# all_pcb.net
KiCad netlist of a schematic drawn in EasyEDA Pro
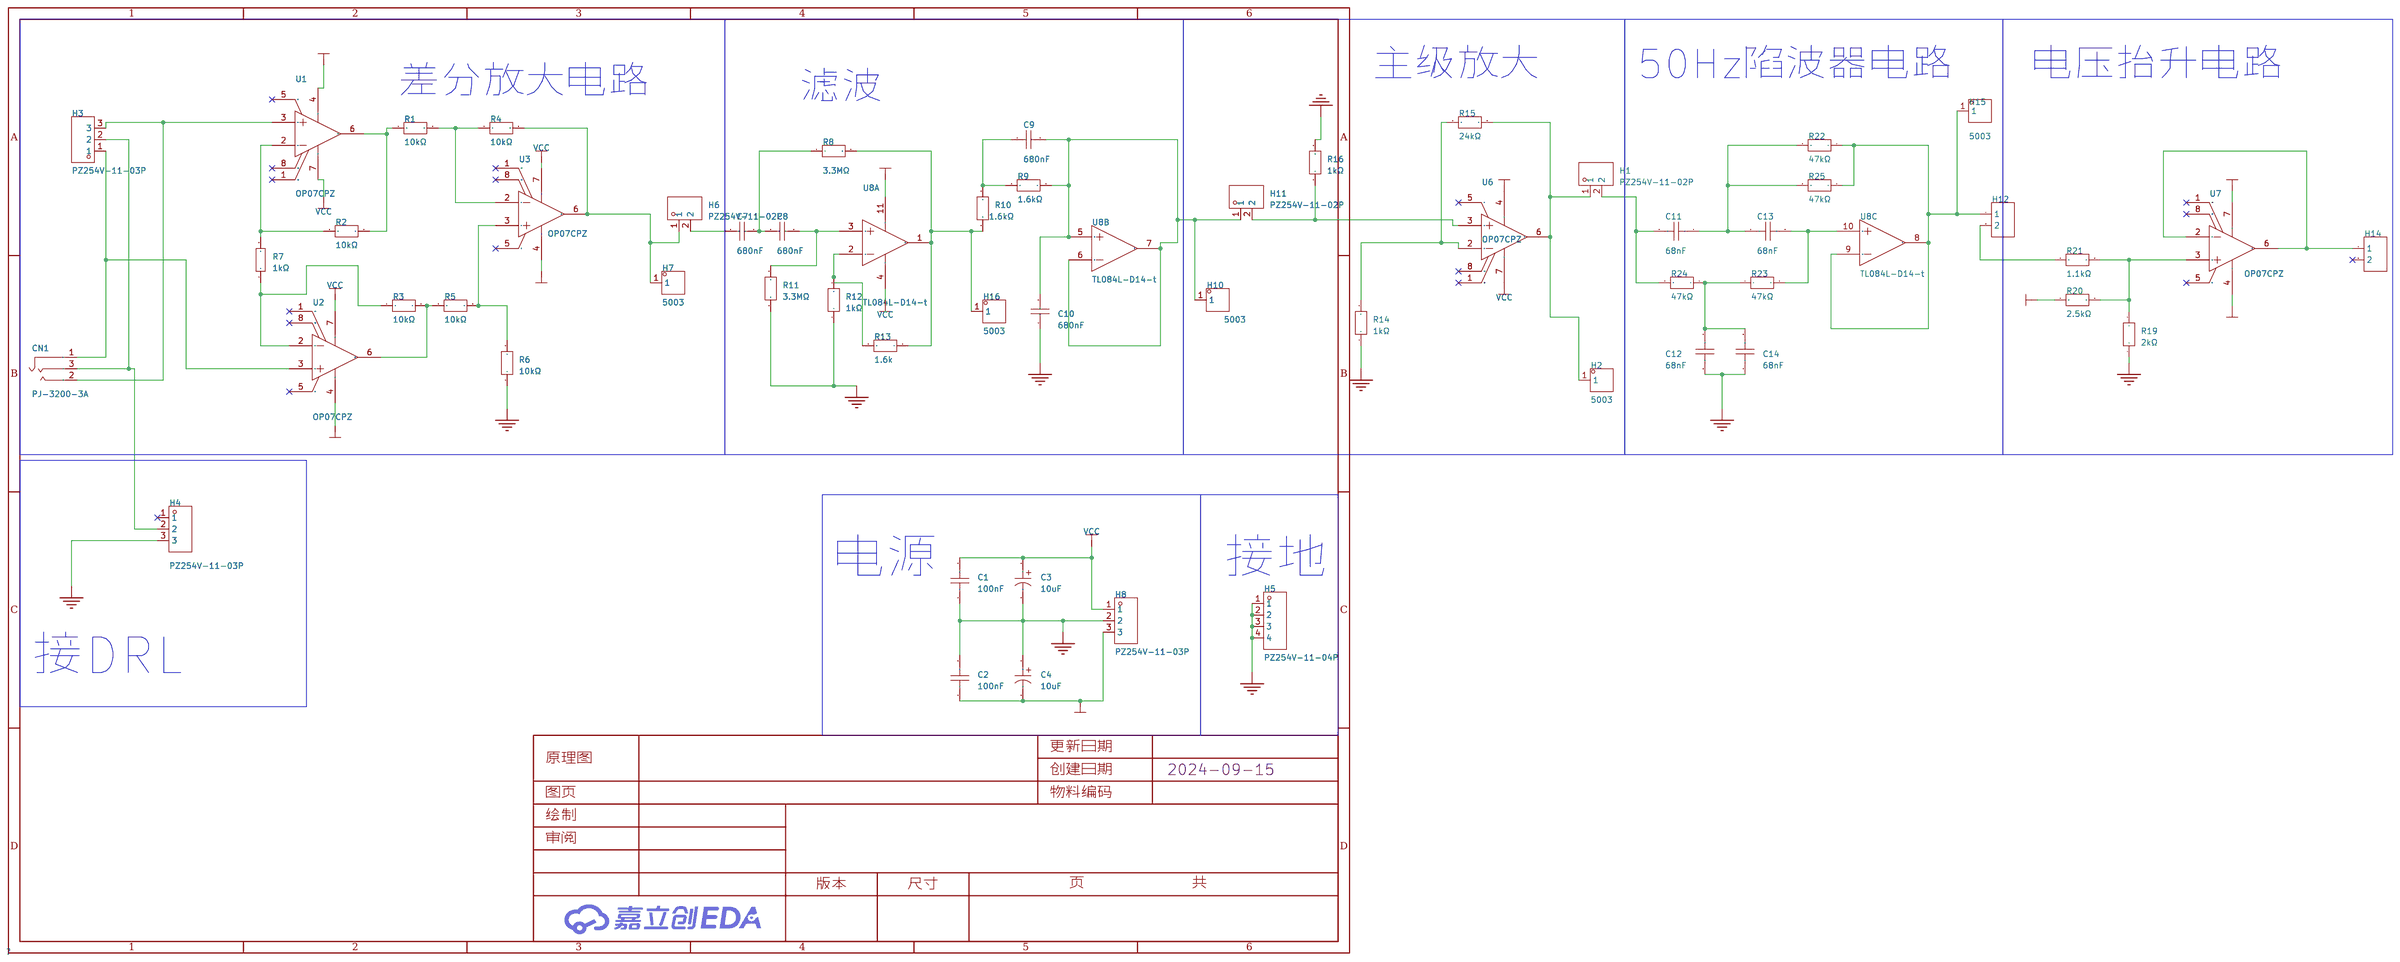
[diagram p0: schematic sheet]

(export (version "E")
  (design (tool "Eeschema 10.0.6"))
  (components
    (comp (ref "C1")
      (value "100nF")
      (footprint "easyedapro:CAP-TH_L13.0-W6.0-P10.0-D0.6")
      (description "容值:100nF;精度:±10%;电压(AC):275V;等级:X2;")
      (fields (field (name "Manufacturer Part") "1X2H410K275-11") (field (name "Manufacturer") "BM(丰明电容)"))
      (libsource (lib "easyedapro") (part "1X2H410K275-11"))
    )
    (comp (ref "C2")
      (value "100nF")
      (footprint "easyedapro:CAP-TH_L13.0-W6.0-P10.0-D0.6")
      (description "容值:100nF;精度:±10%;电压(AC):275V;等级:X2;")
      (fields (field (name "Manufacturer Part") "1X2H410K275-11") (field (name "Manufacturer") "BM(丰明电容)"))
      (libsource (lib "easyedapro") (part "1X2H410K275-11"))
    )
    (comp (ref "C3")
      (value "10uF")
      (footprint "easyedapro:CAP-TH_BD10.0-P5.00-D0.6-FD")
      (description "容值:10uF;精度:±20%;额定电压:250V;纹波电流:175mA@120Hz;等效串联电阻:-;")
      (fields
        (field (name "Manufacturer Part") "UCS2E100MPD1TD")
        (field (name "Manufacturer") "Nichicon(尼吉康)")
      )
      (libsource (lib "easyedapro") (part "UCS2E100MPD1TD"))
    )
    (comp (ref "C4")
      (value "10uF")
      (footprint "easyedapro:CAP-TH_BD10.0-P5.00-D0.6-FD")
      (description "容值:10uF;精度:±20%;额定电压:250V;纹波电流:175mA@120Hz;等效串联电阻:-;")
      (fields
        (field (name "Manufacturer Part") "UCS2E100MPD1TD")
        (field (name "Manufacturer") "Nichicon(尼吉康)")
      )
      (libsource (lib "easyedapro") (part "UCS2E100MPD1TD"))
    )
    (comp (ref "C7")
      (value "680nF")
      (footprint "easyedapro:CAP-TH_L7.5-W6.5-P5.00-D0.5")
      (description "容值:680nF;精度:±5%;额定电压:100V;工作温度:-40°C~+110°C;")
      (fields (field (name "Manufacturer Part") "PE684J2A0502") (field (name "Manufacturer") "KYET(科雅)"))
      (libsource (lib "easyedapro") (part "PE684J2A0502"))
    )
    (comp (ref "C8")
      (value "680nF")
      (footprint "easyedapro:CAP-TH_L7.5-W6.5-P5.00-D0.5")
      (description "容值:680nF;精度:±5%;额定电压:100V;工作温度:-40°C~+110°C;")
      (fields (field (name "Manufacturer Part") "PE684J2A0502") (field (name "Manufacturer") "KYET(科雅)"))
      (libsource (lib "easyedapro") (part "PE684J2A0502"))
    )
    (comp (ref "C9")
      (value "680nF")
      (footprint "easyedapro:CAP-TH_L7.5-W6.5-P5.00-D0.5")
      (description "容值:680nF;精度:±5%;额定电压:100V;工作温度:-40°C~+110°C;")
      (fields (field (name "Manufacturer Part") "PE684J2A0502") (field (name "Manufacturer") "KYET(科雅)"))
      (libsource (lib "easyedapro") (part "PE684J2A0502"))
    )
    (comp (ref "C10")
      (value "680nF")
      (footprint "easyedapro:CAP-TH_L7.5-W6.5-P5.00-D0.5")
      (description "容值:680nF;精度:±5%;额定电压:100V;工作温度:-40°C~+110°C;")
      (fields (field (name "Manufacturer Part") "PE684J2A0502") (field (name "Manufacturer") "KYET(科雅)"))
      (libsource (lib "easyedapro") (part "PE684J2A0502"))
    )
    (comp (ref "C11")
      (value "68nF")
      (footprint "easyedapro:CAP-TH_L5.1-W3.8-P5.08-D1.2")
      (description "容值:100nF;精度:±10%;额定电压:630V;温度系数:X7R;")
      (fields (field (name "Manufacturer Part") "C322C104KBR5TA") (field (name "Manufacturer") "KEMET(基美)"))
      (libsource (lib "easyedapro") (part "C322C104KBR5TA"))
    )
    (comp (ref "C12")
      (value "68nF")
      (footprint "easyedapro:CAP-TH_L18.0-W8.0-P15.00-D0.8")
      (description "容值:200nF;精度:±20%;电压(AC):305V;等级:X2;")
      (fields (field (name "Manufacturer Part") "B32922H3204M") (field (name "Manufacturer") "TDK"))
      (libsource (lib "easyedapro") (part "B32922H3204M"))
    )
    (comp (ref "C13")
      (value "68nF")
      (footprint "easyedapro:CAP-TH_L5.1-W3.8-P5.08-D1.2")
      (description "容值:100nF;精度:±10%;额定电压:630V;温度系数:X7R;")
      (fields (field (name "Manufacturer Part") "C322C104KBR5TA") (field (name "Manufacturer") "KEMET(基美)"))
      (libsource (lib "easyedapro") (part "C322C104KBR5TA"))
    )
    (comp (ref "C14")
      (value "68nF")
      (footprint "easyedapro:CAP-TH_L5.1-W3.8-P5.08-D1.2")
      (description "容值:100nF;精度:±10%;额定电压:630V;温度系数:X7R;")
      (fields (field (name "Manufacturer Part") "C322C104KBR5TA") (field (name "Manufacturer") "KEMET(基美)"))
      (libsource (lib "easyedapro") (part "C322C104KBR5TA"))
    )
    (comp (ref "CN1")
      (value "PJ-3200-3A")
      (footprint "easyedapro:AUDIO-TH_PJ-3200-3A")
      (description "连接器类型:3.5mm耳机座;额定电流:500mA;额定电压:30V;工作温度范围:-20°C~+70°C;")
      (fields (field (name "Manufacturer") "韩国韩荣"))
      (libsource (lib "easyedapro") (part "PJ-3200-3A"))
    )
    (comp (ref "H1")
      (value "PZ254V-11-02P")
      (footprint "easyedapro:HDR-TH_2P-P2.54-V-M")
      (fields (field (name "Manufacturer") "XFCN(兴飞)"))
      (libsource (lib "easyedapro") (part "PZ254V-11-02P"))
    )
    (comp (ref "H2")
      (value "5003")
      (footprint "easyedapro:TEST-TH_BD2.54-P1.39")
      (description "类型:测试环;全长/全高:7.62mm;工作高度:-;接触电阻:-;弹性寿命:-;额定电流:-;额定电压:-;触头材质:磷青铜;触头镀层:-;工作温度范围:-;")
      (fields (field (name "Manufacturer") "Keystone"))
      (libsource (lib "easyedapro") (part "5003"))
    )
    (comp (ref "H3")
      (value "PZ254V-11-03P")
      (footprint "easyedapro:HDR-TH_3P-P2.54-V-M")
      (fields (field (name "Manufacturer") "XFCN(兴飞)"))
      (libsource (lib "easyedapro") (part "PZ254V-11-03P_C2937625"))
    )
    (comp (ref "H4")
      (value "PZ254V-11-03P")
      (footprint "easyedapro:HDR-TH_3P-P2.54-V-M")
      (fields (field (name "Manufacturer") "XFCN(兴飞)"))
      (libsource (lib "easyedapro") (part "PZ254V-11-03P_C2937625"))
    )
    (comp (ref "H5")
      (value "PZ254V-11-04P")
      (footprint "easyedapro:HDR-TH_4P-P2.54-V-M")
      (fields (field (name "Manufacturer") "XFCN(兴飞)"))
      (libsource (lib "easyedapro") (part "PZ254V-11-04P_C2691448"))
    )
    (comp (ref "H6")
      (value "PZ254V-11-02P")
      (footprint "easyedapro:HDR-TH_2P-P2.54-V-M")
      (fields (field (name "Manufacturer") "XFCN(兴飞)"))
      (libsource (lib "easyedapro") (part "PZ254V-11-02P"))
    )
    (comp (ref "H7")
      (value "5003")
      (footprint "easyedapro:TEST-TH_BD2.54-P1.39")
      (description "类型:测试环;全长/全高:7.62mm;工作高度:-;接触电阻:-;弹性寿命:-;额定电流:-;额定电压:-;触头材质:磷青铜;触头镀层:-;工作温度范围:-;")
      (fields (field (name "Manufacturer") "Keystone"))
      (libsource (lib "easyedapro") (part "5003"))
    )
    (comp (ref "H8")
      (value "PZ254V-11-03P")
      (footprint "easyedapro:HDR-TH_3P-P2.54-V-M")
      (fields (field (name "Manufacturer") "XFCN(兴飞)"))
      (libsource (lib "easyedapro") (part "PZ254V-11-03P_C2937625"))
    )
    (comp (ref "H10")
      (value "5003")
      (footprint "easyedapro:TEST-TH_BD2.54-P1.39")
      (description "类型:测试环;全长/全高:7.62mm;工作高度:-;接触电阻:-;弹性寿命:-;额定电流:-;额定电压:-;触头材质:磷青铜;触头镀层:-;工作温度范围:-;")
      (fields (field (name "Manufacturer") "Keystone"))
      (libsource (lib "easyedapro") (part "5003"))
    )
    (comp (ref "H11")
      (value "PZ254V-11-02P")
      (footprint "easyedapro:HDR-TH_2P-P2.54-V-M")
      (fields (field (name "Manufacturer") "XFCN(兴飞)"))
      (libsource (lib "easyedapro") (part "PZ254V-11-02P"))
    )
    (comp (ref "H12")
      (value "~")
      (footprint "easyedapro:HDR-TH_2P-P2.54-V-F")
      (libsource (lib "easyedapro") (part "Header-Female-2.54_1x2"))
    )
    (comp (ref "H14")
      (value "~")
      (footprint "easyedapro:HDR-TH_2P-P2.54-V-F")
      (libsource (lib "easyedapro") (part "Header-Female-2.54_1x2"))
    )
    (comp (ref "H15")
      (value "5003")
      (footprint "easyedapro:TEST-TH_BD2.54-P1.39")
      (description "类型:测试环;全长/全高:7.62mm;工作高度:-;接触电阻:-;弹性寿命:-;额定电流:-;额定电压:-;触头材质:磷青铜;触头镀层:-;工作温度范围:-;")
      (fields (field (name "Manufacturer") "Keystone"))
      (libsource (lib "easyedapro") (part "5003"))
    )
    (comp (ref "H16")
      (value "5003")
      (footprint "easyedapro:TEST-TH_BD2.54-P1.39")
      (description "类型:测试环;全长/全高:7.62mm;工作高度:-;接触电阻:-;弹性寿命:-;额定电流:-;额定电压:-;触头材质:磷青铜;触头镀层:-;工作温度范围:-;")
      (fields (field (name "Manufacturer") "Keystone"))
      (libsource (lib "easyedapro") (part "5003"))
    )
    (comp (ref "R1")
      (value "10kΩ")
      (footprint "easyedapro:RES-TH_BD2.4-L6.3-P10.30-D0.6")
      (description "电阻类型:金属膜电阻;阻值:10kΩ;精度:±1%;功率:250mW;温度系数:±50ppm/°C;")
      (fields
        (field (name "Manufacturer Part") "RN1/4W10KFT/BA1")
        (field (name "Manufacturer") "Tyohm(幸亚电阻)")
      )
      (libsource (lib "easyedapro") (part "RN 1/4W 10K F T/B A1"))
    )
    (comp (ref "R2")
      (value "10kΩ")
      (footprint "easyedapro:RES-TH_BD2.4-L6.3-P10.30-D0.6")
      (description "电阻类型:金属膜电阻;阻值:10kΩ;精度:±1%;功率:250mW;温度系数:±50ppm/°C;")
      (fields
        (field (name "Manufacturer Part") "RN1/4W10KFT/BA1")
        (field (name "Manufacturer") "Tyohm(幸亚电阻)")
      )
      (libsource (lib "easyedapro") (part "RN 1/4W 10K F T/B A1"))
    )
    (comp (ref "R3")
      (value "10kΩ")
      (footprint "easyedapro:RES-TH_BD2.4-L6.3-P10.30-D0.6")
      (description "电阻类型:金属膜电阻;阻值:10kΩ;精度:±1%;功率:250mW;温度系数:±50ppm/°C;")
      (fields
        (field (name "Manufacturer Part") "RN1/4W10KFT/BA1")
        (field (name "Manufacturer") "Tyohm(幸亚电阻)")
      )
      (libsource (lib "easyedapro") (part "RN 1/4W 10K F T/B A1"))
    )
    (comp (ref "R4")
      (value "10kΩ")
      (footprint "easyedapro:RES-TH_BD2.4-L6.3-P10.30-D0.6")
      (description "电阻类型:金属膜电阻;阻值:10kΩ;精度:±1%;功率:250mW;温度系数:±50ppm/°C;")
      (fields
        (field (name "Manufacturer Part") "RN1/4W10KFT/BA1")
        (field (name "Manufacturer") "Tyohm(幸亚电阻)")
      )
      (libsource (lib "easyedapro") (part "RN 1/4W 10K F T/B A1"))
    )
    (comp (ref "R5")
      (value "10kΩ")
      (footprint "easyedapro:RES-TH_BD2.4-L6.3-P10.30-D0.6")
      (description "电阻类型:金属膜电阻;阻值:10kΩ;精度:±1%;功率:250mW;温度系数:±50ppm/°C;")
      (fields
        (field (name "Manufacturer Part") "RN1/4W10KFT/BA1")
        (field (name "Manufacturer") "Tyohm(幸亚电阻)")
      )
      (libsource (lib "easyedapro") (part "RN 1/4W 10K F T/B A1"))
    )
    (comp (ref "R6")
      (value "10kΩ")
      (footprint "easyedapro:RES-TH_BD2.4-L6.3-P10.30-D0.6")
      (description "电阻类型:金属膜电阻;阻值:10kΩ;精度:±1%;功率:250mW;温度系数:±50ppm/°C;")
      (fields
        (field (name "Manufacturer Part") "RN1/4W10KFT/BA1")
        (field (name "Manufacturer") "Tyohm(幸亚电阻)")
      )
      (libsource (lib "easyedapro") (part "RN 1/4W 10K F T/B A1"))
    )
    (comp (ref "R7")
      (value "1kΩ")
      (footprint "easyedapro:RES-TH_BD2.5-L6.5-P10.50-D0.6")
      (description "电阻类型:金属膜电阻;阻值:1kΩ;精度:±1%;功率:250mW;温度系数:±50ppm/°C;")
      (fields
        (field (name "Manufacturer Part") "MFR0W4F1001A50")
        (field (name "Manufacturer") "UNI-ROYAL(厚声)")
      )
      (libsource (lib "easyedapro") (part "MFR0W4F1001A50"))
    )
    (comp (ref "R8")
      (value "3.3MΩ")
      (footprint "easyedapro:RES-TH_BD2.4-L6.3-P10.30-D0.6")
      (description "电阻类型:金属膜电阻;阻值:10kΩ;精度:±1%;功率:250mW;温度系数:±50ppm/°C;")
      (fields
        (field (name "Manufacturer Part") "RN1/4W10KFT/BA1")
        (field (name "Manufacturer") "Tyohm(幸亚电阻)")
      )
      (libsource (lib "easyedapro") (part "RN 1/4W 10K F T/B A1"))
    )
    (comp (ref "R9")
      (value "1.6kΩ")
      (footprint "easyedapro:RES-TH_BD2.4-L6.3-P10.30-D0.6")
      (description "电阻类型:金属膜电阻;阻值:10kΩ;精度:±1%;功率:250mW;温度系数:±50ppm/°C;")
      (fields
        (field (name "Manufacturer Part") "RN1/4W10KFT/BA1")
        (field (name "Manufacturer") "Tyohm(幸亚电阻)")
      )
      (libsource (lib "easyedapro") (part "RN 1/4W 10K F T/B A1"))
    )
    (comp (ref "R10")
      (value "1.6kΩ")
      (footprint "easyedapro:RES-TH_BD2.4-L6.3-P10.30-D0.6")
      (description "电阻类型:金属膜电阻;阻值:10kΩ;精度:±1%;功率:250mW;温度系数:±50ppm/°C;")
      (fields
        (field (name "Manufacturer Part") "RN1/4W10KFT/BA1")
        (field (name "Manufacturer") "Tyohm(幸亚电阻)")
      )
      (libsource (lib "easyedapro") (part "RN 1/4W 10K F T/B A1"))
    )
    (comp (ref "R11")
      (value "3.3MΩ")
      (footprint "easyedapro:RES-TH_BD2.4-L6.3-P10.30-D0.6")
      (description "电阻类型:金属膜电阻;阻值:10kΩ;精度:±1%;功率:250mW;温度系数:±50ppm/°C;")
      (fields
        (field (name "Manufacturer Part") "RN1/4W10KFT/BA1")
        (field (name "Manufacturer") "Tyohm(幸亚电阻)")
      )
      (libsource (lib "easyedapro") (part "RN 1/4W 10K F T/B A1"))
    )
    (comp (ref "R12")
      (value "1kΩ")
      (footprint "easyedapro:RES-TH_BD2.4-L6.3-P10.30-D0.6")
      (description "电阻类型:金属膜电阻;阻值:10kΩ;精度:±1%;功率:250mW;温度系数:±50ppm/°C;")
      (fields
        (field (name "Manufacturer Part") "RN1/4W10KFT/BA1")
        (field (name "Manufacturer") "Tyohm(幸亚电阻)")
      )
      (libsource (lib "easyedapro") (part "RN 1/4W 10K F T/B A1"))
    )
    (comp (ref "R13")
      (value "1.6k")
      (footprint "easyedapro:RES-TH_BD2.4-L6.3-P10.30-D0.6")
      (description "电阻类型:金属膜电阻;阻值:10kΩ;精度:±1%;功率:250mW;温度系数:±50ppm/°C;")
      (fields
        (field (name "Manufacturer Part") "RN1/4W10KFT/BA1")
        (field (name "Manufacturer") "Tyohm(幸亚电阻)")
      )
      (libsource (lib "easyedapro") (part "RN 1/4W 10K F T/B A1"))
    )
    (comp (ref "R14")
      (value "1kΩ")
      (footprint "easyedapro:RES-TH_BD2.4-L6.3-P10.30-D0.6")
      (description "电阻类型:金属膜电阻;阻值:10kΩ;精度:±1%;功率:250mW;温度系数:±50ppm/°C;")
      (fields
        (field (name "Manufacturer Part") "RN1/4W10KFT/BA1")
        (field (name "Manufacturer") "Tyohm(幸亚电阻)")
      )
      (libsource (lib "easyedapro") (part "RN 1/4W 10K F T/B A1"))
    )
    (comp (ref "R15")
      (value "24kΩ")
      (footprint "easyedapro:RES-TH_BD2.4-L6.3-P10.30-D0.6")
      (description "电阻类型:金属膜电阻;阻值:10kΩ;精度:±1%;功率:250mW;温度系数:±50ppm/°C;")
      (fields
        (field (name "Manufacturer Part") "RN1/4W10KFT/BA1")
        (field (name "Manufacturer") "Tyohm(幸亚电阻)")
      )
      (libsource (lib "easyedapro") (part "RN 1/4W 10K F T/B A1"))
    )
    (comp (ref "R16")
      (value "1kΩ")
      (footprint "easyedapro:RES-TH_BD2.4-L6.3-P10.30-D0.6")
      (description "电阻类型:金属膜电阻;阻值:10kΩ;精度:±1%;功率:250mW;温度系数:±50ppm/°C;")
      (fields
        (field (name "Manufacturer Part") "RN1/4W10KFT/BA1")
        (field (name "Manufacturer") "Tyohm(幸亚电阻)")
      )
      (libsource (lib "easyedapro") (part "RN 1/4W 10K F T/B A1"))
    )
    (comp (ref "R19")
      (value "2kΩ")
      (footprint "easyedapro:RES-TH_BD2.3-L6.5-P10.50-D0.5")
      (description "电阻类型:金属膜电阻;阻值:2kΩ;精度:±1%;功率:250mW;温度系数:±200ppm/°C;")
      (fields (field (name "Manufacturer Part") "MF1/4W-2KΩ±1%T52") (field (name "Manufacturer") "华星机电"))
      (libsource (lib "easyedapro") (part "MF1/4W-2KΩ±1%T52"))
    )
    (comp (ref "R20")
      (value "2.5kΩ")
      (footprint "easyedapro:RES-TH_BD4.6-L11.4-P15.40-D0.8")
      (description "电阻类型:绕线电阻;阻值:2.5kΩ;精度:±1%;功率:2W;温度系数:±20ppm/°C;")
      (fields (field (name "Manufacturer Part") "WHC2K5FET") (field (name "Manufacturer") "Ohmite"))
      (libsource (lib "easyedapro") (part "WHC2K5FET"))
    )
    (comp (ref "R21")
      (value "1.1kΩ")
      (footprint "easyedapro:RES-TH_BD3.3-L9.0-P13.00-D0.6")
      (description "电阻类型:金属膜电阻;阻值:1.1kΩ;精度:±5%;功率:500mW;温度系数:±300ppm/°C;")
      (fields (field (name "Manufacturer Part") "RSF-50JR-52-1K1") (field (name "Manufacturer") "YAGEO(国巨)"))
      (libsource (lib "easyedapro") (part "RSF-50JR-52-1K1"))
    )
    (comp (ref "R22")
      (value "47kΩ")
      (footprint "easyedapro:RES-TH_BD2.3-L6.5-P10.50-D0.5")
      (description "电阻类型:金属膜电阻;阻值:5.1kΩ;精度:±1%;功率:250mW;温度系数:±200ppm/°C;")
      (fields (field (name "Manufacturer Part") "MF1/4W-5.1KΩ±1%T52") (field (name "Manufacturer") "华星机电"))
      (libsource (lib "easyedapro") (part "MF1/4W-5.1KΩ±1%T52"))
    )
    (comp (ref "R23")
      (value "47kΩ")
      (footprint "easyedapro:RES-TH_BD2.4-L6.5-P10.50-D0.5")
      (description "电阻类型:金属膜电阻;阻值:32kΩ;精度:±0.1%;功率:250mW;温度系数:±25ppm/°C;")
      (fields
        (field (name "Manufacturer Part") "RNF14BTE32K0")
        (field (name "Manufacturer") "SEI(Stackpole Electronics Inc.)")
      )
      (libsource (lib "easyedapro") (part "RNF14BTE32K0"))
    )
    (comp (ref "R24")
      (value "47kΩ")
      (footprint "easyedapro:RES-TH_BD2.4-L6.5-P10.50-D0.5")
      (description "电阻类型:金属膜电阻;阻值:32kΩ;精度:±0.1%;功率:250mW;温度系数:±25ppm/°C;")
      (fields
        (field (name "Manufacturer Part") "RNF14BTE32K0")
        (field (name "Manufacturer") "SEI(Stackpole Electronics Inc.)")
      )
      (libsource (lib "easyedapro") (part "RNF14BTE32K0"))
    )
    (comp (ref "R25")
      (value "47kΩ")
      (footprint "easyedapro:RES-TH_BD3.3-L9.0-P13.00-D0.6")
      (description "电阻类型:金属膜电阻;阻值:16kΩ;精度:±5%;功率:500mW;温度系数:±300ppm/°C;")
      (fields (field (name "Manufacturer Part") "RSF-50JT-52-16K") (field (name "Manufacturer") "YAGEO(国巨)"))
      (libsource (lib "easyedapro") (part "RSF-50JT-52-16K"))
    )
    (comp (ref "U1")
      (value "OP07CPZ")
      (footprint "easyedapro:PDIP-8_L9.3-W6.4-P2.54-LS7.6-BL")
      (description "超低失调电压运算放大器")
      (fields (field (name "Manufacturer") "ADI(亚德诺)"))
      (libsource (lib "easyedapro") (part "OP07CPZ"))
    )
    (comp (ref "U2")
      (value "OP07CPZ")
      (footprint "easyedapro:PDIP-8_L9.3-W6.4-P2.54-LS7.6-BL")
      (description "超低失调电压运算放大器")
      (fields (field (name "Manufacturer") "ADI(亚德诺)"))
      (libsource (lib "easyedapro") (part "OP07CPZ"))
    )
    (comp (ref "U3")
      (value "OP07CPZ")
      (footprint "easyedapro:PDIP-8_L9.3-W6.4-P2.54-LS7.6-BL")
      (description "超低失调电压运算放大器")
      (fields (field (name "Manufacturer") "ADI(亚德诺)"))
      (libsource (lib "easyedapro") (part "OP07CPZ"))
    )
    (comp (ref "U6")
      (value "OP07CPZ")
      (footprint "easyedapro:PDIP-8_L9.3-W6.4-P2.54-LS7.6-BL")
      (description "超低失调电压运算放大器")
      (fields (field (name "Manufacturer") "ADI(亚德诺)"))
      (libsource (lib "easyedapro") (part "OP07CPZ"))
    )
    (comp (ref "U7")
      (value "OP07CPZ")
      (footprint "easyedapro:PDIP-8_L9.3-W6.4-P2.54-LS7.6-BL")
      (description "超低失调电压运算放大器")
      (fields (field (name "Manufacturer") "ADI(亚德诺)"))
      (libsource (lib "easyedapro") (part "OP07CPZ"))
    )
    (comp (ref "U8")
      (value "TL084L-D14-t")
      (footprint "easyedapro:PDIP-14_L19.3-W6.5-P2.54-LS7.6-BL")
      (fields (field (name "Manufacturer") "UTC(友顺)"))
      (libsource (lib "easyedapro") (part "TL084L"))
    )
  )
  (nets
    (net (code "1") (name "GND") (class "Default")
      (node (ref "C1") (pin "1") (pinfunction "1_1") (pintype "unspecified"))
      (node (ref "C10") (pin "1") (pinfunction "1_1") (pintype "input"))
      (node (ref "C12") (pin "2") (pinfunction "2_2") (pintype "unspecified"))
      (node (ref "C14") (pin "1") (pinfunction "1_1") (pintype "unspecified"))
      (node (ref "C2") (pin "2") (pinfunction "2_2") (pintype "unspecified"))
      (node (ref "C3") (pin "2") (pinfunction "2_2") (pintype "input"))
      (node (ref "C4") (pin "1") (pinfunction "1_1") (pintype "input"))
      (node (ref "H4") (pin "3") (pinfunction "3_3") (pintype "unspecified"))
      (node (ref "H5") (pin "1") (pinfunction "1_1") (pintype "unspecified"))
      (node (ref "H5") (pin "2") (pinfunction "2_2") (pintype "unspecified"))
      (node (ref "H5") (pin "3") (pinfunction "3_3") (pintype "unspecified"))
      (node (ref "H5") (pin "4") (pinfunction "4_4") (pintype "unspecified"))
      (node (ref "H8") (pin "2") (pinfunction "2_2") (pintype "unspecified"))
      (node (ref "R11") (pin "1") (pinfunction "1_1") (pintype "unspecified"))
      (node (ref "R12") (pin "1") (pinfunction "1_1") (pintype "unspecified"))
      (node (ref "R14") (pin "1") (pinfunction "1_1") (pintype "unspecified"))
      (node (ref "R16") (pin "2") (pinfunction "2_2") (pintype "unspecified"))
      (node (ref "R19") (pin "1") (pinfunction "1_1") (pintype "unspecified"))
      (node (ref "R6") (pin "1") (pinfunction "1_1") (pintype "unspecified"))
    )
    (net (code "2") (name "Net-(C7-Pad1)") (class "Default")
      (node (ref "C7") (pin "1") (pinfunction "1_1") (pintype "input"))
      (node (ref "H6") (pin "2") (pinfunction "2_2") (pintype "unspecified"))
    )
    (net (code "3") (name "Net-(C7-Pad2)") (class "Default")
      (node (ref "C7") (pin "2") (pinfunction "2_2") (pintype "input"))
      (node (ref "C8") (pin "1") (pinfunction "1_1") (pintype "input"))
      (node (ref "R8") (pin "1") (pinfunction "1_1") (pintype "unspecified"))
    )
    (net (code "4") (name "Net-(C9-Pad1)") (class "Default")
      (node (ref "C9") (pin "1") (pinfunction "1_1") (pintype "input"))
      (node (ref "R10") (pin "2") (pinfunction "2_2") (pintype "unspecified"))
      (node (ref "R9") (pin "1") (pinfunction "1_1") (pintype "unspecified"))
    )
    (net (code "5") (name "Net-(C11-Pad1)") (class "Default")
      (node (ref "C11") (pin "1") (pinfunction "1_1") (pintype "unspecified"))
      (node (ref "C13") (pin "1") (pinfunction "1_1") (pintype "unspecified"))
      (node (ref "R22") (pin "2") (pinfunction "2_2") (pintype "unspecified"))
      (node (ref "R25") (pin "2") (pinfunction "2_2") (pintype "unspecified"))
    )
    (net (code "6") (name "Net-(C11-Pad2)") (class "Default")
      (node (ref "C11") (pin "2") (pinfunction "2_2") (pintype "unspecified"))
      (node (ref "H1") (pin "2") (pinfunction "2_2") (pintype "unspecified"))
      (node (ref "R24") (pin "2") (pinfunction "2_2") (pintype "unspecified"))
    )
    (net (code "7") (name "Net-(C12-Pad1)") (class "Default")
      (node (ref "C12") (pin "1") (pinfunction "1_1") (pintype "unspecified"))
      (node (ref "C14") (pin "2") (pinfunction "2_2") (pintype "unspecified"))
      (node (ref "R23") (pin "1") (pinfunction "1_1") (pintype "unspecified"))
      (node (ref "R24") (pin "1") (pinfunction "1_1") (pintype "unspecified"))
    )
    (net (code "8") (name "Net-(CN1-Pad3)") (class "Default")
      (node (ref "CN1") (pin "3") (pinfunction "3_3") (pintype "unspecified"))
      (node (ref "H3") (pin "2") (pinfunction "2_2") (pintype "unspecified"))
      (node (ref "H4") (pin "2") (pinfunction "2_2") (pintype "unspecified"))
    )
    (net (code "9") (name "Net-(H12-Pad2)") (class "Default")
      (node (ref "H12") (pin "2") (pinfunction "2_2") (pintype "input"))
      (node (ref "R21") (pin "1") (pinfunction "1_1") (pintype "input"))
    )
    (net (code "10") (name "Net-(U1-IN+)") (class "Default")
      (node (ref "CN1") (pin "2") (pinfunction "2_2") (pintype "unspecified"))
      (node (ref "H3") (pin "3") (pinfunction "3_3") (pintype "unspecified"))
      (node (ref "U1") (pin "3") (pinfunction "IN+_3") (pintype "unspecified"))
    )
    (net (code "11") (name "Net-(U1-IN-)") (class "Default")
      (node (ref "R2") (pin "2") (pinfunction "2_2") (pintype "unspecified"))
      (node (ref "R7") (pin "2") (pinfunction "2_2") (pintype "input"))
      (node (ref "U1") (pin "2") (pinfunction "IN-_2") (pintype "unspecified"))
    )
    (net (code "12") (name "Net-(U1-OUT)") (class "Default")
      (node (ref "R1") (pin "1") (pinfunction "1_1") (pintype "unspecified"))
      (node (ref "R2") (pin "1") (pinfunction "1_1") (pintype "unspecified"))
      (node (ref "U1") (pin "6") (pinfunction "OUT_6") (pintype "output"))
    )
    (net (code "13") (name "Net-(U2-IN+)") (class "Default")
      (node (ref "CN1") (pin "1") (pinfunction "1_1") (pintype "unspecified"))
      (node (ref "H3") (pin "1") (pinfunction "1_1") (pintype "unspecified"))
      (node (ref "U2") (pin "3") (pinfunction "IN+_3") (pintype "unspecified"))
    )
    (net (code "14") (name "Net-(U2-IN-)") (class "Default")
      (node (ref "R3") (pin "1") (pinfunction "1_1") (pintype "unspecified"))
      (node (ref "R7") (pin "1") (pinfunction "1_1") (pintype "input"))
      (node (ref "U2") (pin "2") (pinfunction "IN-_2") (pintype "unspecified"))
    )
    (net (code "15") (name "Net-(U2-OUT)") (class "Default")
      (node (ref "R3") (pin "2") (pinfunction "2_2") (pintype "unspecified"))
      (node (ref "R5") (pin "1") (pinfunction "1_1") (pintype "unspecified"))
      (node (ref "U2") (pin "6") (pinfunction "OUT_6") (pintype "output"))
    )
    (net (code "16") (name "Net-(U3-IN+)") (class "Default")
      (node (ref "R5") (pin "2") (pinfunction "2_2") (pintype "unspecified"))
      (node (ref "R6") (pin "2") (pinfunction "2_2") (pintype "unspecified"))
      (node (ref "U3") (pin "3") (pinfunction "IN+_3") (pintype "unspecified"))
    )
    (net (code "17") (name "Net-(U3-IN-)") (class "Default")
      (node (ref "R1") (pin "2") (pinfunction "2_2") (pintype "unspecified"))
      (node (ref "R4") (pin "1") (pinfunction "1_1") (pintype "unspecified"))
      (node (ref "U3") (pin "2") (pinfunction "IN-_2") (pintype "unspecified"))
    )
    (net (code "18") (name "Net-(U3-OUT)") (class "Default")
      (node (ref "H6") (pin "1") (pinfunction "1_1") (pintype "unspecified"))
      (node (ref "H7") (pin "1") (pinfunction "1_1") (pintype "unspecified"))
      (node (ref "R4") (pin "2") (pinfunction "2_2") (pintype "unspecified"))
      (node (ref "U3") (pin "6") (pinfunction "OUT_6") (pintype "output"))
    )
    (net (code "19") (name "Net-(U6-IN+)") (class "Default")
      (node (ref "H11") (pin "2") (pinfunction "2_2") (pintype "unspecified"))
      (node (ref "R16") (pin "1") (pinfunction "1_1") (pintype "unspecified"))
      (node (ref "U6") (pin "3") (pinfunction "IN+_3") (pintype "unspecified"))
    )
    (net (code "20") (name "Net-(U6-IN-)") (class "Default")
      (node (ref "R14") (pin "2") (pinfunction "2_2") (pintype "unspecified"))
      (node (ref "R15") (pin "1") (pinfunction "1_1") (pintype "unspecified"))
      (node (ref "U6") (pin "2") (pinfunction "IN-_2") (pintype "unspecified"))
    )
    (net (code "21") (name "Net-(U6-OUT)") (class "Default")
      (node (ref "H1") (pin "1") (pinfunction "1_1") (pintype "unspecified"))
      (node (ref "H2") (pin "1") (pinfunction "1_1") (pintype "unspecified"))
      (node (ref "R15") (pin "2") (pinfunction "2_2") (pintype "unspecified"))
      (node (ref "U6") (pin "6") (pinfunction "OUT_6") (pintype "output"))
    )
    (net (code "22") (name "Net-(U7-IN+)") (class "Default")
      (node (ref "R19") (pin "2") (pinfunction "2_2") (pintype "unspecified"))
      (node (ref "R20") (pin "2") (pinfunction "2_2") (pintype "unspecified"))
      (node (ref "R21") (pin "2") (pinfunction "2_2") (pintype "input"))
      (node (ref "U7") (pin "3") (pinfunction "IN+_3") (pintype "unspecified"))
    )
    (net (code "23") (name "Net-(U7-IN-)") (class "Default")
      (node (ref "H14") (pin "1") (pinfunction "1_1") (pintype "input"))
      (node (ref "U7") (pin "2") (pinfunction "IN-_2") (pintype "unspecified"))
      (node (ref "U7") (pin "6") (pinfunction "OUT_6") (pintype "output"))
    )
    (net (code "24") (name "Net-(U8A-IN1+)") (class "Default")
      (node (ref "C8") (pin "2") (pinfunction "2_2") (pintype "input"))
      (node (ref "R11") (pin "2") (pinfunction "2_2") (pintype "unspecified"))
      (node (ref "U8") (pin "3") (pinfunction "IN1+_3") (pintype "unspecified"))
    )
    (net (code "25") (name "Net-(U8A-IN1-)") (class "Default")
      (node (ref "R12") (pin "2") (pinfunction "2_2") (pintype "unspecified"))
      (node (ref "R13") (pin "2") (pinfunction "2_2") (pintype "unspecified"))
      (node (ref "U8") (pin "2") (pinfunction "IN1-_2") (pintype "unspecified"))
    )
    (net (code "26") (name "Net-(U8A-OUT1)") (class "Default")
      (node (ref "H16") (pin "1") (pinfunction "1_1") (pintype "unspecified"))
      (node (ref "R10") (pin "1") (pinfunction "1_1") (pintype "unspecified"))
      (node (ref "R13") (pin "1") (pinfunction "1_1") (pintype "unspecified"))
      (node (ref "R8") (pin "2") (pinfunction "2_2") (pintype "unspecified"))
      (node (ref "U8") (pin "1") (pinfunction "OUT1_1") (pintype "output"))
    )
    (net (code "27") (name "Net-(U8B-IN2+)") (class "Default")
      (node (ref "C10") (pin "2") (pinfunction "2_2") (pintype "input"))
      (node (ref "C9") (pin "2") (pinfunction "2_2") (pintype "input"))
      (node (ref "H10") (pin "1") (pinfunction "1_1") (pintype "unspecified"))
      (node (ref "H11") (pin "1") (pinfunction "1_1") (pintype "unspecified"))
      (node (ref "R9") (pin "2") (pinfunction "2_2") (pintype "unspecified"))
      (node (ref "U8") (pin "5") (pinfunction "IN2+_5") (pintype "unspecified"))
      (node (ref "U8") (pin "6") (pinfunction "IN2-_6") (pintype "unspecified"))
      (node (ref "U8") (pin "7") (pinfunction "OUT2_7") (pintype "output"))
    )
    (net (code "28") (name "Net-(U8C-IN3+)") (class "Default")
      (node (ref "C13") (pin "2") (pinfunction "2_2") (pintype "unspecified"))
      (node (ref "R23") (pin "2") (pinfunction "2_2") (pintype "unspecified"))
      (node (ref "U8") (pin "10") (pinfunction "IN3+_10") (pintype "unspecified"))
    )
    (net (code "29") (name "Net-(U8C-IN3-)") (class "Default")
      (node (ref "H12") (pin "1") (pinfunction "1_1") (pintype "input"))
      (node (ref "H15") (pin "1") (pinfunction "1_1") (pintype "unspecified"))
      (node (ref "R22") (pin "1") (pinfunction "1_1") (pintype "unspecified"))
      (node (ref "R25") (pin "1") (pinfunction "1_1") (pintype "unspecified"))
      (node (ref "U8") (pin "8") (pinfunction "OUT3_8") (pintype "output"))
      (node (ref "U8") (pin "9") (pinfunction "IN3-_9") (pintype "unspecified"))
    )
    (net (code "30") (name "VCC") (class "Default")
      (node (ref "C1") (pin "2") (pinfunction "2_2") (pintype "unspecified"))
      (node (ref "C3") (pin "1") (pinfunction "1_1") (pintype "input"))
      (node (ref "H8") (pin "1") (pinfunction "1_1") (pintype "unspecified"))
      (node (ref "R20") (pin "1") (pinfunction "1_1") (pintype "unspecified"))
      (node (ref "U1") (pin "7") (pinfunction "V+_7") (pintype "unspecified"))
      (node (ref "U2") (pin "7") (pinfunction "V+_7") (pintype "unspecified"))
      (node (ref "U3") (pin "7") (pinfunction "V+_7") (pintype "unspecified"))
      (node (ref "U6") (pin "7") (pinfunction "V+_7") (pintype "unspecified"))
      (node (ref "U7") (pin "7") (pinfunction "V+_7") (pintype "unspecified"))
      (node (ref "U8") (pin "4") (pinfunction "V+_4") (pintype "unspecified"))
    )
    (net (code "31") (name "VEE") (class "Default")
      (node (ref "C2") (pin "1") (pinfunction "1_1") (pintype "unspecified"))
      (node (ref "C4") (pin "2") (pinfunction "2_2") (pintype "input"))
      (node (ref "H8") (pin "3") (pinfunction "3_3") (pintype "unspecified"))
      (node (ref "U1") (pin "4") (pinfunction "V-_4") (pintype "unspecified"))
      (node (ref "U2") (pin "4") (pinfunction "V-_4") (pintype "unspecified"))
      (node (ref "U3") (pin "4") (pinfunction "V-_4") (pintype "unspecified"))
      (node (ref "U6") (pin "4") (pinfunction "V-_4") (pintype "unspecified"))
      (node (ref "U7") (pin "4") (pinfunction "V-_4") (pintype "unspecified"))
      (node (ref "U8") (pin "11") (pinfunction "V-_11") (pintype "unspecified"))
    )
    (net (code "32") (name "unconnected-(H4-Pad1)") (class "Default")
      (node (ref "H4") (pin "1") (pinfunction "1_1") (pintype "unspecified+no_connect"))
    )
    (net (code "33") (name "unconnected-(H14-Pad2)") (class "Default")
      (node (ref "H14") (pin "2") (pinfunction "2_2") (pintype "input+no_connect"))
    )
    (net (code "34") (name "unconnected-(U1-NC-Pad5)") (class "Default")
      (node (ref "U1") (pin "5") (pinfunction "NC_5") (pintype "unspecified+no_connect"))
    )
    (net (code "35") (name "unconnected-(U1-VOS_TRIM-Pad1)") (class "Default")
      (node (ref "U1") (pin "1") (pinfunction "VOS_TRIM_1") (pintype "unspecified+no_connect"))
    )
    (net (code "36") (name "unconnected-(U1-VOS_TRIM-Pad8)") (class "Default")
      (node (ref "U1") (pin "8") (pinfunction "VOS_TRIM_8") (pintype "unspecified+no_connect"))
    )
    (net (code "37") (name "unconnected-(U2-NC-Pad5)") (class "Default")
      (node (ref "U2") (pin "5") (pinfunction "NC_5") (pintype "unspecified+no_connect"))
    )
    (net (code "38") (name "unconnected-(U2-VOS_TRIM-Pad1)") (class "Default")
      (node (ref "U2") (pin "1") (pinfunction "VOS_TRIM_1") (pintype "unspecified+no_connect"))
    )
    (net (code "39") (name "unconnected-(U2-VOS_TRIM-Pad8)") (class "Default")
      (node (ref "U2") (pin "8") (pinfunction "VOS_TRIM_8") (pintype "unspecified+no_connect"))
    )
    (net (code "40") (name "unconnected-(U3-NC-Pad5)") (class "Default")
      (node (ref "U3") (pin "5") (pinfunction "NC_5") (pintype "unspecified+no_connect"))
    )
    (net (code "41") (name "unconnected-(U3-VOS_TRIM-Pad1)") (class "Default")
      (node (ref "U3") (pin "1") (pinfunction "VOS_TRIM_1") (pintype "unspecified+no_connect"))
    )
    (net (code "42") (name "unconnected-(U3-VOS_TRIM-Pad8)") (class "Default")
      (node (ref "U3") (pin "8") (pinfunction "VOS_TRIM_8") (pintype "unspecified+no_connect"))
    )
    (net (code "43") (name "unconnected-(U6-NC-Pad5)") (class "Default")
      (node (ref "U6") (pin "5") (pinfunction "NC_5") (pintype "unspecified+no_connect"))
    )
    (net (code "44") (name "unconnected-(U6-VOS_TRIM-Pad1)") (class "Default")
      (node (ref "U6") (pin "1") (pinfunction "VOS_TRIM_1") (pintype "unspecified+no_connect"))
    )
    (net (code "45") (name "unconnected-(U6-VOS_TRIM-Pad8)") (class "Default")
      (node (ref "U6") (pin "8") (pinfunction "VOS_TRIM_8") (pintype "unspecified+no_connect"))
    )
    (net (code "46") (name "unconnected-(U7-NC-Pad5)") (class "Default")
      (node (ref "U7") (pin "5") (pinfunction "NC_5") (pintype "unspecified+no_connect"))
    )
    (net (code "47") (name "unconnected-(U7-VOS_TRIM-Pad1)") (class "Default")
      (node (ref "U7") (pin "1") (pinfunction "VOS_TRIM_1") (pintype "unspecified+no_connect"))
    )
    (net (code "48") (name "unconnected-(U7-VOS_TRIM-Pad8)") (class "Default")
      (node (ref "U7") (pin "8") (pinfunction "VOS_TRIM_8") (pintype "unspecified+no_connect"))
    )
  )
)
